# R107X.net
KiCad netlist of a schematic drawn in EAGLE
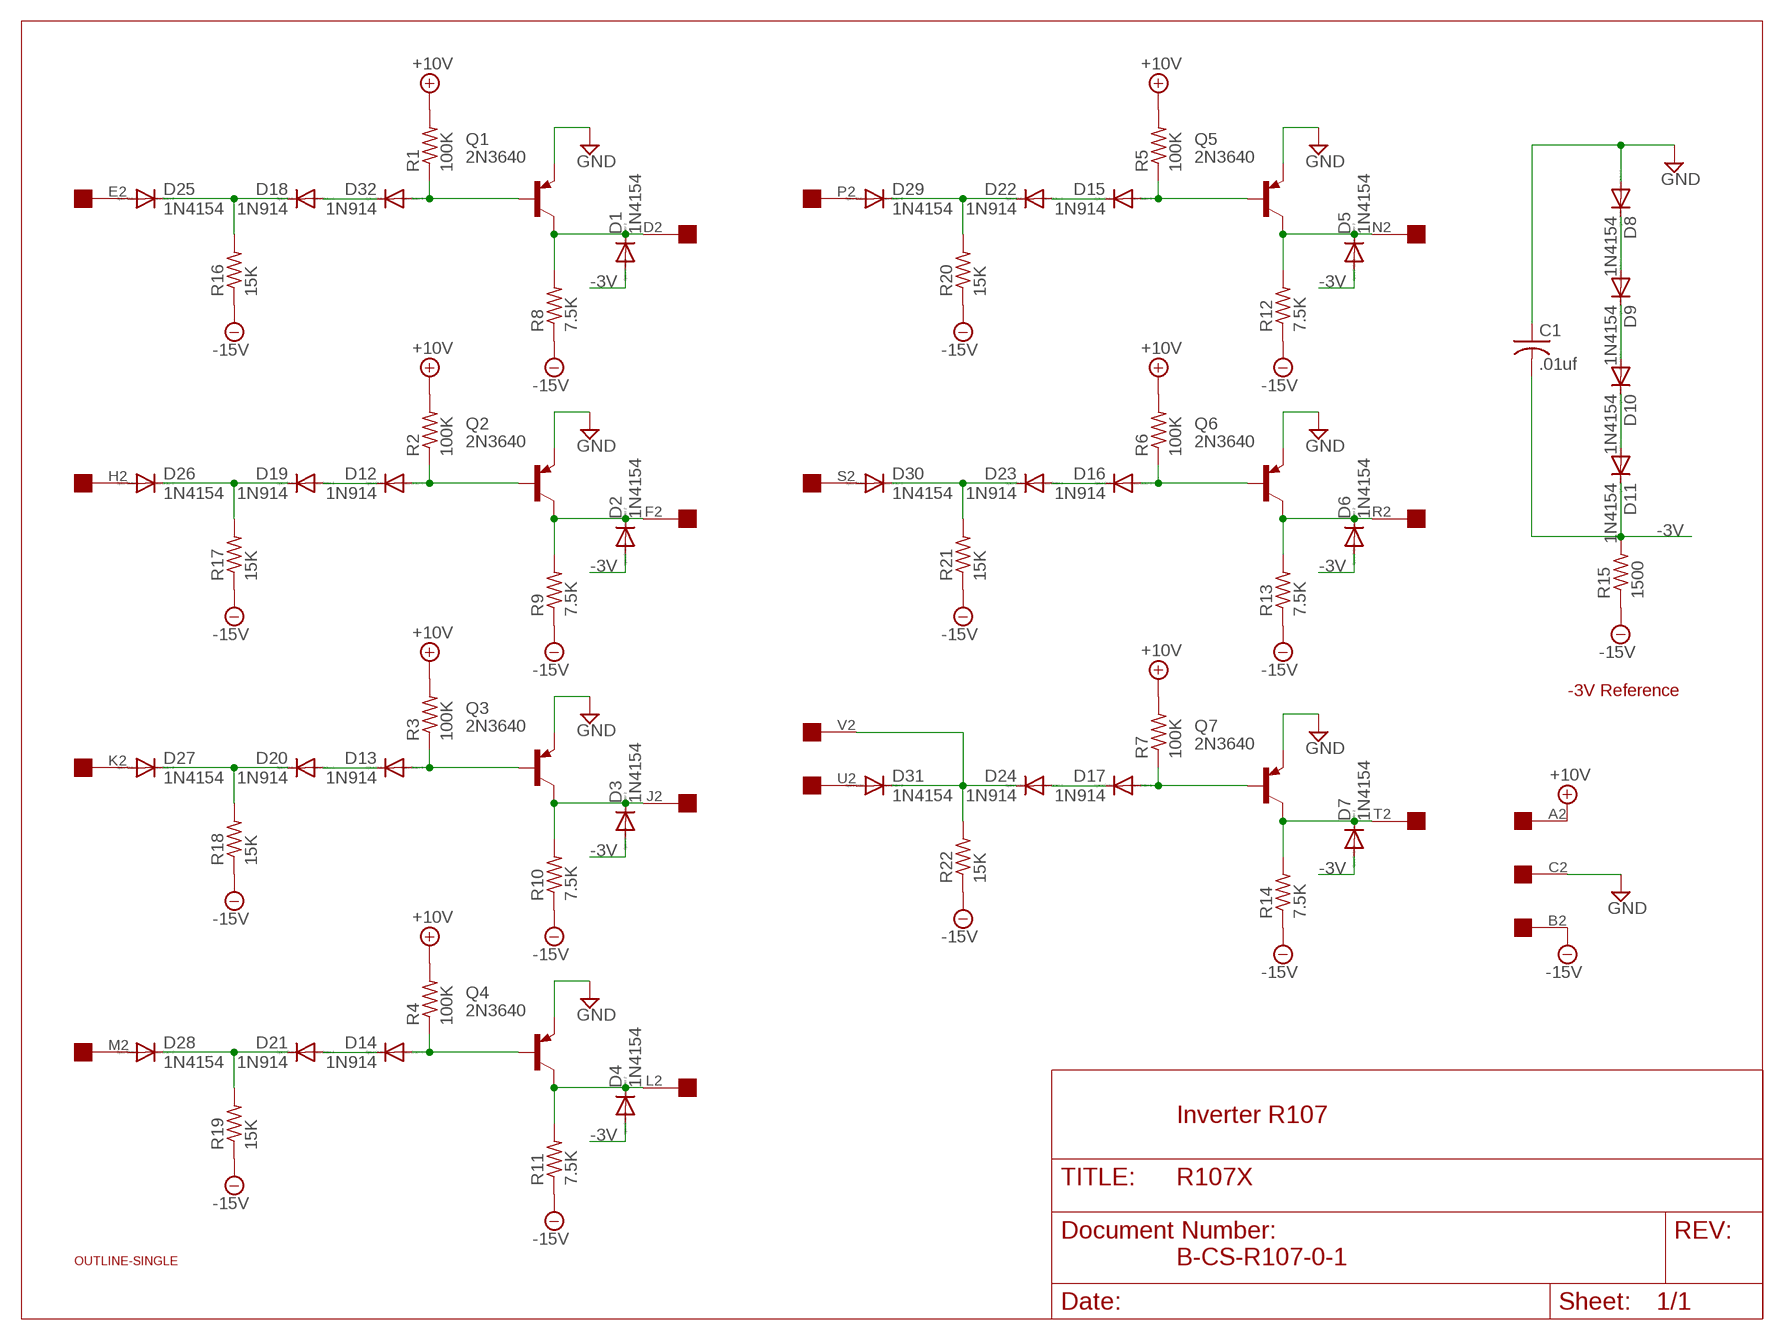
[diagram p0: schematic, sheet 1]

(export (version "E")
  (design (tool "Eeschema 10.0.6"))
  (components
    (comp (ref "C1")
      (value ".01uf")
      (footprint "eagle-import:C050-025X075")
      (libsource (lib "eagle-import") (part "C-US050-025X075"))
    )
    (comp (ref "D1")
      (value "1N4154")
      (footprint "eagle-import:DO35-10")
      (libsource (lib "eagle-import") (part "1N4148DO35-10"))
    )
    (comp (ref "D2")
      (value "1N4154")
      (footprint "eagle-import:DO35-10")
      (libsource (lib "eagle-import") (part "1N4148DO35-10"))
    )
    (comp (ref "D3")
      (value "1N4154")
      (footprint "eagle-import:DO35-10")
      (libsource (lib "eagle-import") (part "1N4148DO35-10"))
    )
    (comp (ref "D4")
      (value "1N4154")
      (footprint "eagle-import:DO35-10")
      (libsource (lib "eagle-import") (part "1N4148DO35-10"))
    )
    (comp (ref "D5")
      (value "1N4154")
      (footprint "eagle-import:DO35-10")
      (libsource (lib "eagle-import") (part "1N4148DO35-10"))
    )
    (comp (ref "D6")
      (value "1N4154")
      (footprint "eagle-import:DO35-10")
      (libsource (lib "eagle-import") (part "1N4148DO35-10"))
    )
    (comp (ref "D7")
      (value "1N4154")
      (footprint "eagle-import:DO35-10")
      (libsource (lib "eagle-import") (part "1N4148DO35-10"))
    )
    (comp (ref "D8")
      (value "1N4154")
      (footprint "eagle-import:DO35-10")
      (libsource (lib "eagle-import") (part "1N4148DO35-10"))
    )
    (comp (ref "D9")
      (value "1N4154")
      (footprint "eagle-import:DO35-10")
      (libsource (lib "eagle-import") (part "1N4148DO35-10"))
    )
    (comp (ref "D10")
      (value "1N4154")
      (footprint "eagle-import:DO35-10")
      (libsource (lib "eagle-import") (part "1N4148DO35-10"))
    )
    (comp (ref "D11")
      (value "1N4154")
      (footprint "eagle-import:DO35-10")
      (libsource (lib "eagle-import") (part "1N4148DO35-10"))
    )
    (comp (ref "D12")
      (value "1N914")
      (footprint "eagle-import:DO35-10")
      (libsource (lib "eagle-import") (part "1N4148DO35-10"))
    )
    (comp (ref "D13")
      (value "1N914")
      (footprint "eagle-import:DO35-10")
      (libsource (lib "eagle-import") (part "1N4148DO35-10"))
    )
    (comp (ref "D14")
      (value "1N914")
      (footprint "eagle-import:DO35-10")
      (libsource (lib "eagle-import") (part "1N4148DO35-10"))
    )
    (comp (ref "D15")
      (value "1N914")
      (footprint "eagle-import:DO35-10")
      (libsource (lib "eagle-import") (part "1N4148DO35-10"))
    )
    (comp (ref "D16")
      (value "1N914")
      (footprint "eagle-import:DO35-10")
      (libsource (lib "eagle-import") (part "1N4148DO35-10"))
    )
    (comp (ref "D17")
      (value "1N914")
      (footprint "eagle-import:DO35-10")
      (libsource (lib "eagle-import") (part "1N4148DO35-10"))
    )
    (comp (ref "D18")
      (value "1N914")
      (footprint "eagle-import:DO35-10")
      (libsource (lib "eagle-import") (part "1N4148DO35-10"))
    )
    (comp (ref "D19")
      (value "1N914")
      (footprint "eagle-import:DO35-10")
      (libsource (lib "eagle-import") (part "1N4148DO35-10"))
    )
    (comp (ref "D20")
      (value "1N914")
      (footprint "eagle-import:DO35-10")
      (libsource (lib "eagle-import") (part "1N4148DO35-10"))
    )
    (comp (ref "D21")
      (value "1N914")
      (footprint "eagle-import:DO35-10")
      (libsource (lib "eagle-import") (part "1N4148DO35-10"))
    )
    (comp (ref "D22")
      (value "1N914")
      (footprint "eagle-import:DO35-10")
      (libsource (lib "eagle-import") (part "1N4148DO35-10"))
    )
    (comp (ref "D23")
      (value "1N914")
      (footprint "eagle-import:DO35-10")
      (libsource (lib "eagle-import") (part "1N4148DO35-10"))
    )
    (comp (ref "D24")
      (value "1N914")
      (footprint "eagle-import:DO35-10")
      (libsource (lib "eagle-import") (part "1N4148DO35-10"))
    )
    (comp (ref "D25")
      (value "1N4154")
      (footprint "eagle-import:DO35-10")
      (libsource (lib "eagle-import") (part "1N4148DO35-10"))
    )
    (comp (ref "D26")
      (value "1N4154")
      (footprint "eagle-import:DO35-10")
      (libsource (lib "eagle-import") (part "1N4148DO35-10"))
    )
    (comp (ref "D27")
      (value "1N4154")
      (footprint "eagle-import:DO35-10")
      (libsource (lib "eagle-import") (part "1N4148DO35-10"))
    )
    (comp (ref "D28")
      (value "1N4154")
      (footprint "eagle-import:DO35-10")
      (libsource (lib "eagle-import") (part "1N4148DO35-10"))
    )
    (comp (ref "D29")
      (value "1N4154")
      (footprint "eagle-import:DO35-10")
      (libsource (lib "eagle-import") (part "1N4148DO35-10"))
    )
    (comp (ref "D30")
      (value "1N4154")
      (footprint "eagle-import:DO35-10")
      (libsource (lib "eagle-import") (part "1N4148DO35-10"))
    )
    (comp (ref "D31")
      (value "1N4154")
      (footprint "eagle-import:DO35-10")
      (libsource (lib "eagle-import") (part "1N4148DO35-10"))
    )
    (comp (ref "D32")
      (value "1N914")
      (footprint "eagle-import:DO35-10")
      (libsource (lib "eagle-import") (part "1N4148DO35-10"))
    )
    (comp (ref "Q1")
      (value "2N3640")
      (footprint "eagle-import:TO39")
      (libsource (lib "eagle-import") (part "2N3637"))
    )
    (comp (ref "Q2")
      (value "2N3640")
      (footprint "eagle-import:TO39")
      (libsource (lib "eagle-import") (part "2N3637"))
    )
    (comp (ref "Q3")
      (value "2N3640")
      (footprint "eagle-import:TO39")
      (libsource (lib "eagle-import") (part "2N3637"))
    )
    (comp (ref "Q4")
      (value "2N3640")
      (footprint "eagle-import:TO39")
      (libsource (lib "eagle-import") (part "2N3637"))
    )
    (comp (ref "Q5")
      (value "2N3640")
      (footprint "eagle-import:TO39")
      (libsource (lib "eagle-import") (part "2N3637"))
    )
    (comp (ref "Q6")
      (value "2N3640")
      (footprint "eagle-import:TO39")
      (libsource (lib "eagle-import") (part "2N3637"))
    )
    (comp (ref "Q7")
      (value "2N3640")
      (footprint "eagle-import:TO39")
      (libsource (lib "eagle-import") (part "2N3637"))
    )
    (comp (ref "R1")
      (value "100K")
      (footprint "eagle-import:0207_10")
      (libsource (lib "eagle-import") (part "R-US_0207/10"))
    )
    (comp (ref "R2")
      (value "100K")
      (footprint "eagle-import:0207_10")
      (libsource (lib "eagle-import") (part "R-US_0207/10"))
    )
    (comp (ref "R3")
      (value "100K")
      (footprint "eagle-import:0207_10")
      (libsource (lib "eagle-import") (part "R-US_0207/10"))
    )
    (comp (ref "R4")
      (value "100K")
      (footprint "eagle-import:0207_10")
      (libsource (lib "eagle-import") (part "R-US_0207/10"))
    )
    (comp (ref "R5")
      (value "100K")
      (footprint "eagle-import:0207_10")
      (libsource (lib "eagle-import") (part "R-US_0207/10"))
    )
    (comp (ref "R6")
      (value "100K")
      (footprint "eagle-import:0207_10")
      (libsource (lib "eagle-import") (part "R-US_0207/10"))
    )
    (comp (ref "R7")
      (value "100K")
      (footprint "eagle-import:0207_10")
      (libsource (lib "eagle-import") (part "R-US_0207/10"))
    )
    (comp (ref "R8")
      (value "7.5K")
      (footprint "eagle-import:0207_10")
      (libsource (lib "eagle-import") (part "R-US_0207/10"))
    )
    (comp (ref "R9")
      (value "7.5K")
      (footprint "eagle-import:0207_10")
      (libsource (lib "eagle-import") (part "R-US_0207/10"))
    )
    (comp (ref "R10")
      (value "7.5K")
      (footprint "eagle-import:0207_10")
      (libsource (lib "eagle-import") (part "R-US_0207/10"))
    )
    (comp (ref "R11")
      (value "7.5K")
      (footprint "eagle-import:0207_10")
      (libsource (lib "eagle-import") (part "R-US_0207/10"))
    )
    (comp (ref "R12")
      (value "7.5K")
      (footprint "eagle-import:0207_10")
      (libsource (lib "eagle-import") (part "R-US_0207/10"))
    )
    (comp (ref "R13")
      (value "7.5K")
      (footprint "eagle-import:0207_10")
      (libsource (lib "eagle-import") (part "R-US_0207/10"))
    )
    (comp (ref "R14")
      (value "7.5K")
      (footprint "eagle-import:0207_10")
      (libsource (lib "eagle-import") (part "R-US_0207/10"))
    )
    (comp (ref "R15")
      (value "1500")
      (footprint "eagle-import:0207_10")
      (libsource (lib "eagle-import") (part "R-US_0207/10"))
    )
    (comp (ref "R16")
      (value "15K")
      (footprint "eagle-import:0207_10")
      (libsource (lib "eagle-import") (part "R-US_0207/10"))
    )
    (comp (ref "R17")
      (value "15K")
      (footprint "eagle-import:0207_10")
      (libsource (lib "eagle-import") (part "R-US_0207/10"))
    )
    (comp (ref "R18")
      (value "15K")
      (footprint "eagle-import:0207_10")
      (libsource (lib "eagle-import") (part "R-US_0207/10"))
    )
    (comp (ref "R19")
      (value "15K")
      (footprint "eagle-import:0207_10")
      (libsource (lib "eagle-import") (part "R-US_0207/10"))
    )
    (comp (ref "R20")
      (value "15K")
      (footprint "eagle-import:0207_10")
      (libsource (lib "eagle-import") (part "R-US_0207/10"))
    )
    (comp (ref "R21")
      (value "15K")
      (footprint "eagle-import:0207_10")
      (libsource (lib "eagle-import") (part "R-US_0207/10"))
    )
    (comp (ref "R22")
      (value "15K")
      (footprint "eagle-import:0207_10")
      (libsource (lib "eagle-import") (part "R-US_0207/10"))
    )
    (comp (ref "U$1")
      (value "OUTLINE-SINGLE")
      (footprint "eagle-import:SINGLE")
      (libsource (lib "eagle-import") (part "OUTLINE-SINGLE"))
    )
    (comp (ref "U$2")
      (value "EDGE-1")
      (footprint "eagle-import:EDGE-CON1")
      (libsource (lib "eagle-import") (part "EDGE-1"))
    )
  )
  (nets
    (net (code "1") (name "+10V") (class "Default")
      (node (ref "R1") (pin "2") (pinfunction "2_2") (pintype "passive"))
      (node (ref "R2") (pin "2") (pinfunction "2_2") (pintype "passive"))
      (node (ref "R3") (pin "2") (pinfunction "2_2") (pintype "passive"))
      (node (ref "R4") (pin "2") (pinfunction "2_2") (pintype "passive"))
      (node (ref "R5") (pin "2") (pinfunction "2_2") (pintype "passive"))
      (node (ref "R6") (pin "2") (pinfunction "2_2") (pintype "passive"))
      (node (ref "R7") (pin "2") (pinfunction "2_2") (pintype "passive"))
      (node (ref "U$2") (pin "A2") (pinfunction "1_A2") (pintype "bidirectional"))
    )
    (net (code "2") (name "-15V") (class "Default")
      (node (ref "R10") (pin "1") (pinfunction "1_1") (pintype "passive"))
      (node (ref "R11") (pin "1") (pinfunction "1_1") (pintype "passive"))
      (node (ref "R12") (pin "1") (pinfunction "1_1") (pintype "passive"))
      (node (ref "R13") (pin "1") (pinfunction "1_1") (pintype "passive"))
      (node (ref "R14") (pin "1") (pinfunction "1_1") (pintype "passive"))
      (node (ref "R15") (pin "1") (pinfunction "1_1") (pintype "passive"))
      (node (ref "R16") (pin "1") (pinfunction "1_1") (pintype "passive"))
      (node (ref "R17") (pin "1") (pinfunction "1_1") (pintype "passive"))
      (node (ref "R18") (pin "1") (pinfunction "1_1") (pintype "passive"))
      (node (ref "R19") (pin "1") (pinfunction "1_1") (pintype "passive"))
      (node (ref "R20") (pin "1") (pinfunction "1_1") (pintype "passive"))
      (node (ref "R21") (pin "1") (pinfunction "1_1") (pintype "passive"))
      (node (ref "R22") (pin "1") (pinfunction "1_1") (pintype "passive"))
      (node (ref "R8") (pin "1") (pinfunction "1_1") (pintype "passive"))
      (node (ref "R9") (pin "1") (pinfunction "1_1") (pintype "passive"))
      (node (ref "U$2") (pin "B2") (pinfunction "1_B2") (pintype "bidirectional"))
    )
    (net (code "3") (name "/-3V") (class "Default")
      (node (ref "C1") (pin "2") (pinfunction "2_2") (pintype "passive"))
      (node (ref "D1") (pin "A") (pinfunction "A_A") (pintype "passive"))
      (node (ref "D11") (pin "C") (pinfunction "C_C") (pintype "passive"))
      (node (ref "D2") (pin "A") (pinfunction "A_A") (pintype "passive"))
      (node (ref "D3") (pin "A") (pinfunction "A_A") (pintype "passive"))
      (node (ref "D4") (pin "A") (pinfunction "A_A") (pintype "passive"))
      (node (ref "D5") (pin "A") (pinfunction "A_A") (pintype "passive"))
      (node (ref "D6") (pin "A") (pinfunction "A_A") (pintype "passive"))
      (node (ref "D7") (pin "A") (pinfunction "A_A") (pintype "passive"))
      (node (ref "R15") (pin "2") (pinfunction "2_2") (pintype "passive"))
    )
    (net (code "4") (name "GND") (class "Default")
      (node (ref "C1") (pin "1") (pinfunction "1_1") (pintype "passive"))
      (node (ref "D8") (pin "A") (pinfunction "A_A") (pintype "passive"))
      (node (ref "Q1") (pin "1") (pinfunction "E_1") (pintype "passive"))
      (node (ref "Q2") (pin "1") (pinfunction "E_1") (pintype "passive"))
      (node (ref "Q3") (pin "1") (pinfunction "E_1") (pintype "passive"))
      (node (ref "Q4") (pin "1") (pinfunction "E_1") (pintype "passive"))
      (node (ref "Q5") (pin "1") (pinfunction "E_1") (pintype "passive"))
      (node (ref "Q6") (pin "1") (pinfunction "E_1") (pintype "passive"))
      (node (ref "Q7") (pin "1") (pinfunction "E_1") (pintype "passive"))
      (node (ref "U$2") (pin "C2") (pinfunction "1_C2") (pintype "bidirectional"))
    )
    (net (code "5") (name "Net-(D8-PadC)") (class "Default")
      (node (ref "D8") (pin "C") (pinfunction "C_C") (pintype "passive"))
      (node (ref "D9") (pin "A") (pinfunction "A_A") (pintype "passive"))
    )
    (net (code "6") (name "Net-(D10-PadA)") (class "Default")
      (node (ref "D10") (pin "A") (pinfunction "A_A") (pintype "passive"))
      (node (ref "D9") (pin "C") (pinfunction "C_C") (pintype "passive"))
    )
    (net (code "7") (name "Net-(D10-PadC)") (class "Default")
      (node (ref "D10") (pin "C") (pinfunction "C_C") (pintype "passive"))
      (node (ref "D11") (pin "A") (pinfunction "A_A") (pintype "passive"))
    )
    (net (code "8") (name "Net-(D12-PadC)") (class "Default")
      (node (ref "D12") (pin "C") (pinfunction "C_C") (pintype "passive"))
      (node (ref "D19") (pin "A") (pinfunction "A_A") (pintype "passive"))
    )
    (net (code "9") (name "Net-(D13-PadC)") (class "Default")
      (node (ref "D13") (pin "C") (pinfunction "C_C") (pintype "passive"))
      (node (ref "D20") (pin "A") (pinfunction "A_A") (pintype "passive"))
    )
    (net (code "10") (name "Net-(D14-PadC)") (class "Default")
      (node (ref "D14") (pin "C") (pinfunction "C_C") (pintype "passive"))
      (node (ref "D21") (pin "A") (pinfunction "A_A") (pintype "passive"))
    )
    (net (code "11") (name "Net-(D15-PadC)") (class "Default")
      (node (ref "D15") (pin "C") (pinfunction "C_C") (pintype "passive"))
      (node (ref "D22") (pin "A") (pinfunction "A_A") (pintype "passive"))
    )
    (net (code "12") (name "Net-(D16-PadC)") (class "Default")
      (node (ref "D16") (pin "C") (pinfunction "C_C") (pintype "passive"))
      (node (ref "D23") (pin "A") (pinfunction "A_A") (pintype "passive"))
    )
    (net (code "13") (name "Net-(D17-PadC)") (class "Default")
      (node (ref "D17") (pin "C") (pinfunction "C_C") (pintype "passive"))
      (node (ref "D24") (pin "A") (pinfunction "A_A") (pintype "passive"))
    )
    (net (code "14") (name "Net-(D18-PadA)") (class "Default")
      (node (ref "D18") (pin "A") (pinfunction "A_A") (pintype "passive"))
      (node (ref "D32") (pin "C") (pinfunction "C_C") (pintype "passive"))
    )
    (net (code "15") (name "Net-(D18-PadC)") (class "Default")
      (node (ref "D18") (pin "C") (pinfunction "C_C") (pintype "passive"))
      (node (ref "D25") (pin "C") (pinfunction "C_C") (pintype "passive"))
      (node (ref "R16") (pin "2") (pinfunction "2_2") (pintype "passive"))
    )
    (net (code "16") (name "Net-(D19-PadC)") (class "Default")
      (node (ref "D19") (pin "C") (pinfunction "C_C") (pintype "passive"))
      (node (ref "D26") (pin "C") (pinfunction "C_C") (pintype "passive"))
      (node (ref "R17") (pin "2") (pinfunction "2_2") (pintype "passive"))
    )
    (net (code "17") (name "Net-(D20-PadC)") (class "Default")
      (node (ref "D20") (pin "C") (pinfunction "C_C") (pintype "passive"))
      (node (ref "D27") (pin "C") (pinfunction "C_C") (pintype "passive"))
      (node (ref "R18") (pin "2") (pinfunction "2_2") (pintype "passive"))
    )
    (net (code "18") (name "Net-(D21-PadC)") (class "Default")
      (node (ref "D21") (pin "C") (pinfunction "C_C") (pintype "passive"))
      (node (ref "D28") (pin "C") (pinfunction "C_C") (pintype "passive"))
      (node (ref "R19") (pin "2") (pinfunction "2_2") (pintype "passive"))
    )
    (net (code "19") (name "Net-(D22-PadC)") (class "Default")
      (node (ref "D22") (pin "C") (pinfunction "C_C") (pintype "passive"))
      (node (ref "D29") (pin "C") (pinfunction "C_C") (pintype "passive"))
      (node (ref "R20") (pin "2") (pinfunction "2_2") (pintype "passive"))
    )
    (net (code "20") (name "Net-(D23-PadC)") (class "Default")
      (node (ref "D23") (pin "C") (pinfunction "C_C") (pintype "passive"))
      (node (ref "D30") (pin "C") (pinfunction "C_C") (pintype "passive"))
      (node (ref "R21") (pin "2") (pinfunction "2_2") (pintype "passive"))
    )
    (net (code "21") (name "Net-(Q1-B)") (class "Default")
      (node (ref "D32") (pin "A") (pinfunction "A_A") (pintype "passive"))
      (node (ref "Q1") (pin "2") (pinfunction "B_2") (pintype "passive"))
      (node (ref "R1") (pin "1") (pinfunction "1_1") (pintype "passive"))
    )
    (net (code "22") (name "Net-(Q1-C)") (class "Default")
      (node (ref "D1") (pin "C") (pinfunction "C_C") (pintype "passive"))
      (node (ref "Q1") (pin "3") (pinfunction "C_3") (pintype "passive"))
      (node (ref "R8") (pin "2") (pinfunction "2_2") (pintype "passive"))
      (node (ref "U$2") (pin "D2") (pinfunction "1_D2") (pintype "bidirectional"))
    )
    (net (code "23") (name "Net-(Q2-B)") (class "Default")
      (node (ref "D12") (pin "A") (pinfunction "A_A") (pintype "passive"))
      (node (ref "Q2") (pin "2") (pinfunction "B_2") (pintype "passive"))
      (node (ref "R2") (pin "1") (pinfunction "1_1") (pintype "passive"))
    )
    (net (code "24") (name "Net-(Q2-C)") (class "Default")
      (node (ref "D2") (pin "C") (pinfunction "C_C") (pintype "passive"))
      (node (ref "Q2") (pin "3") (pinfunction "C_3") (pintype "passive"))
      (node (ref "R9") (pin "2") (pinfunction "2_2") (pintype "passive"))
      (node (ref "U$2") (pin "F2") (pinfunction "1_F2") (pintype "bidirectional"))
    )
    (net (code "25") (name "Net-(Q3-B)") (class "Default")
      (node (ref "D13") (pin "A") (pinfunction "A_A") (pintype "passive"))
      (node (ref "Q3") (pin "2") (pinfunction "B_2") (pintype "passive"))
      (node (ref "R3") (pin "1") (pinfunction "1_1") (pintype "passive"))
    )
    (net (code "26") (name "Net-(Q3-C)") (class "Default")
      (node (ref "D3") (pin "C") (pinfunction "C_C") (pintype "passive"))
      (node (ref "Q3") (pin "3") (pinfunction "C_3") (pintype "passive"))
      (node (ref "R10") (pin "2") (pinfunction "2_2") (pintype "passive"))
      (node (ref "U$2") (pin "J2") (pinfunction "1_J2") (pintype "bidirectional"))
    )
    (net (code "27") (name "Net-(Q4-B)") (class "Default")
      (node (ref "D14") (pin "A") (pinfunction "A_A") (pintype "passive"))
      (node (ref "Q4") (pin "2") (pinfunction "B_2") (pintype "passive"))
      (node (ref "R4") (pin "1") (pinfunction "1_1") (pintype "passive"))
    )
    (net (code "28") (name "Net-(Q4-C)") (class "Default")
      (node (ref "D4") (pin "C") (pinfunction "C_C") (pintype "passive"))
      (node (ref "Q4") (pin "3") (pinfunction "C_3") (pintype "passive"))
      (node (ref "R11") (pin "2") (pinfunction "2_2") (pintype "passive"))
      (node (ref "U$2") (pin "L2") (pinfunction "1_L2") (pintype "bidirectional"))
    )
    (net (code "29") (name "Net-(Q5-B)") (class "Default")
      (node (ref "D15") (pin "A") (pinfunction "A_A") (pintype "passive"))
      (node (ref "Q5") (pin "2") (pinfunction "B_2") (pintype "passive"))
      (node (ref "R5") (pin "1") (pinfunction "1_1") (pintype "passive"))
    )
    (net (code "30") (name "Net-(Q5-C)") (class "Default")
      (node (ref "D5") (pin "C") (pinfunction "C_C") (pintype "passive"))
      (node (ref "Q5") (pin "3") (pinfunction "C_3") (pintype "passive"))
      (node (ref "R12") (pin "2") (pinfunction "2_2") (pintype "passive"))
      (node (ref "U$2") (pin "N2") (pinfunction "1_N2") (pintype "bidirectional"))
    )
    (net (code "31") (name "Net-(Q6-B)") (class "Default")
      (node (ref "D16") (pin "A") (pinfunction "A_A") (pintype "passive"))
      (node (ref "Q6") (pin "2") (pinfunction "B_2") (pintype "passive"))
      (node (ref "R6") (pin "1") (pinfunction "1_1") (pintype "passive"))
    )
    (net (code "32") (name "Net-(Q6-C)") (class "Default")
      (node (ref "D6") (pin "C") (pinfunction "C_C") (pintype "passive"))
      (node (ref "Q6") (pin "3") (pinfunction "C_3") (pintype "passive"))
      (node (ref "R13") (pin "2") (pinfunction "2_2") (pintype "passive"))
      (node (ref "U$2") (pin "R2") (pinfunction "1_R2") (pintype "bidirectional"))
    )
    (net (code "33") (name "Net-(Q7-B)") (class "Default")
      (node (ref "D17") (pin "A") (pinfunction "A_A") (pintype "passive"))
      (node (ref "Q7") (pin "2") (pinfunction "B_2") (pintype "passive"))
      (node (ref "R7") (pin "1") (pinfunction "1_1") (pintype "passive"))
    )
    (net (code "34") (name "Net-(Q7-C)") (class "Default")
      (node (ref "D7") (pin "C") (pinfunction "C_C") (pintype "passive"))
      (node (ref "Q7") (pin "3") (pinfunction "C_3") (pintype "passive"))
      (node (ref "R14") (pin "2") (pinfunction "2_2") (pintype "passive"))
      (node (ref "U$2") (pin "T2") (pinfunction "1_T2") (pintype "bidirectional"))
    )
    (net (code "35") (name "Net-(U$2E-1)") (class "Default")
      (node (ref "D25") (pin "A") (pinfunction "A_A") (pintype "passive"))
      (node (ref "U$2") (pin "E2") (pinfunction "1_E2") (pintype "bidirectional"))
    )
    (net (code "36") (name "Net-(U$2G-1)") (class "Default")
      (node (ref "D26") (pin "A") (pinfunction "A_A") (pintype "passive"))
      (node (ref "U$2") (pin "H2") (pinfunction "1_H2") (pintype "bidirectional"))
    )
    (net (code "37") (name "Net-(U$2I-1)") (class "Default")
      (node (ref "D27") (pin "A") (pinfunction "A_A") (pintype "passive"))
      (node (ref "U$2") (pin "K2") (pinfunction "1_K2") (pintype "bidirectional"))
    )
    (net (code "38") (name "Net-(U$2K-1)") (class "Default")
      (node (ref "D28") (pin "A") (pinfunction "A_A") (pintype "passive"))
      (node (ref "U$2") (pin "M2") (pinfunction "1_M2") (pintype "bidirectional"))
    )
    (net (code "39") (name "Net-(U$2M-1)") (class "Default")
      (node (ref "D29") (pin "A") (pinfunction "A_A") (pintype "passive"))
      (node (ref "U$2") (pin "P2") (pinfunction "1_P2") (pintype "bidirectional"))
    )
    (net (code "40") (name "Net-(U$2O-1)") (class "Default")
      (node (ref "D30") (pin "A") (pinfunction "A_A") (pintype "passive"))
      (node (ref "U$2") (pin "S2") (pinfunction "1_S2") (pintype "bidirectional"))
    )
    (net (code "41") (name "Net-(U$2Q-1)") (class "Default")
      (node (ref "D31") (pin "A") (pinfunction "A_A") (pintype "passive"))
      (node (ref "U$2") (pin "U2") (pinfunction "1_U2") (pintype "bidirectional"))
    )
    (net (code "42") (name "Net-(U$2R-1)") (class "Default")
      (node (ref "D24") (pin "C") (pinfunction "C_C") (pintype "passive"))
      (node (ref "D31") (pin "C") (pinfunction "C_C") (pintype "passive"))
      (node (ref "R22") (pin "2") (pinfunction "2_2") (pintype "passive"))
      (node (ref "U$2") (pin "V2") (pinfunction "1_V2") (pintype "bidirectional"))
    )
  )
)
